# RH_T_SENSOR.net
KiCad netlist of a schematic drawn in EAGLE
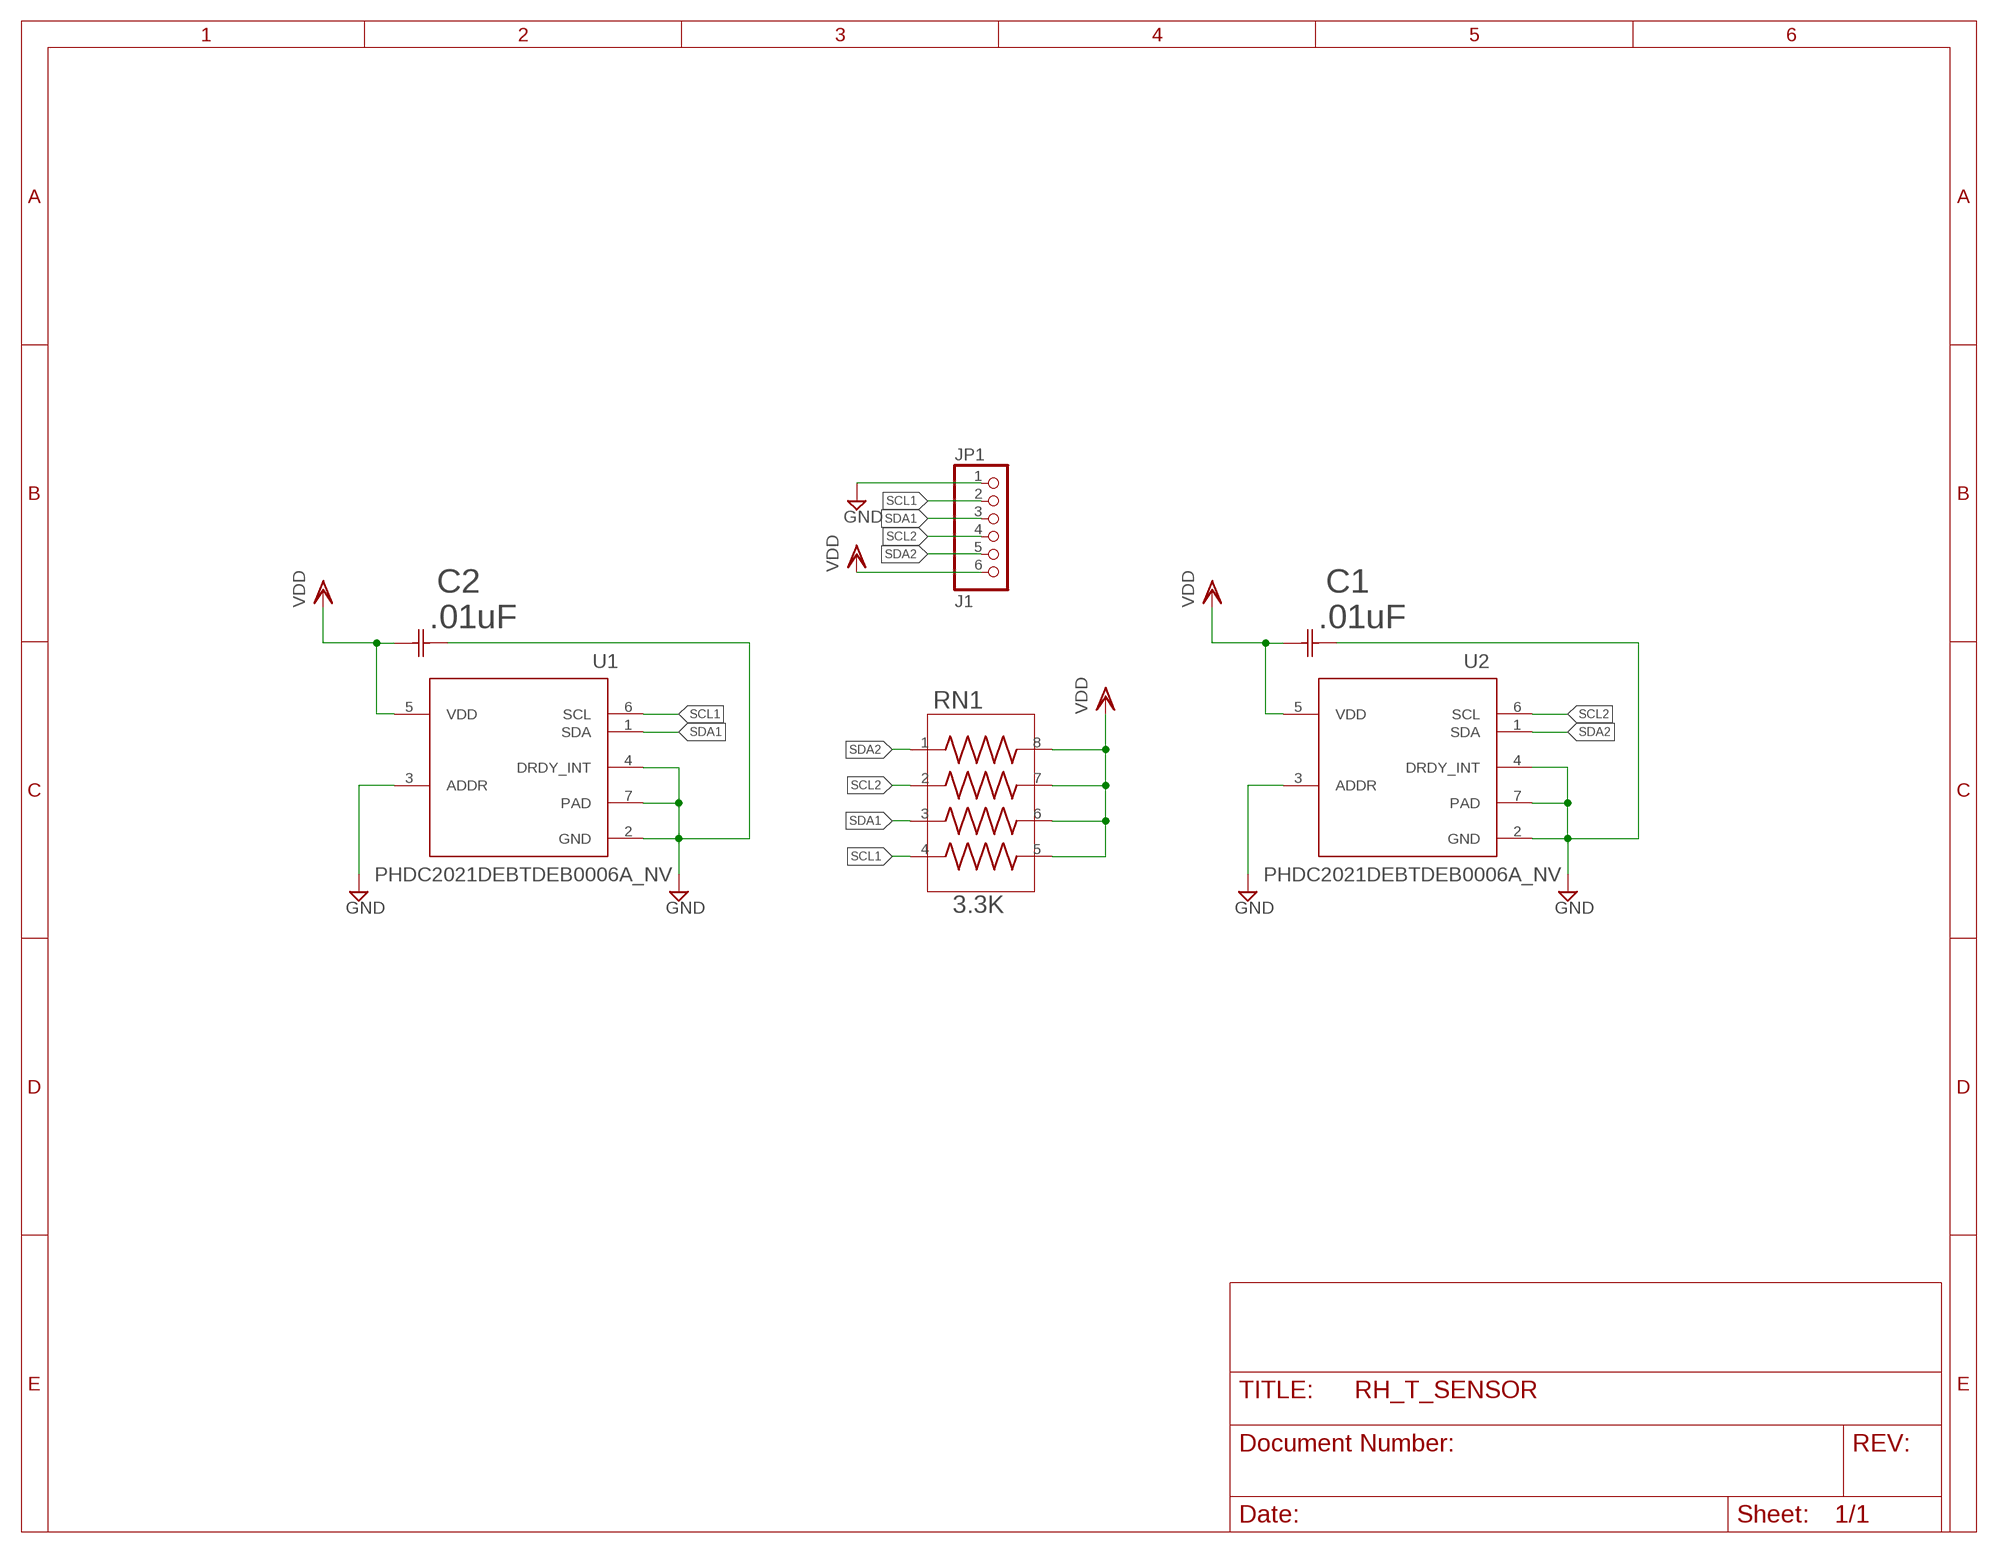
[diagram p0: schematic, sheet 1]

(export (version "E")
  (design (tool "Eeschema 10.0.6"))
  (components
    (comp (ref "C1")
      (value ".01uF")
      (footprint "eagle-import:0402_AVX")
      (fields
        (field (name "MANUFACTURER_PART_NUMBER") "0402YC104KAT2A")
        (field (name "COPYRIGHT") "Copyright (C) 2023 Ultra Librarian. All rights reserved.")
      )
      (libsource (lib "eagle-import") (part "0402YC104KAT2A0402_AVX"))
    )
    (comp (ref "C2")
      (value ".01uF")
      (footprint "eagle-import:0402_AVX")
      (fields
        (field (name "MANUFACTURER_PART_NUMBER") "0402YC104KAT2A")
        (field (name "COPYRIGHT") "Copyright (C) 2023 Ultra Librarian. All rights reserved.")
      )
      (libsource (lib "eagle-import") (part "0402YC104KAT2A0402_AVX"))
    )
    (comp (ref "JP1")
      (value "J1")
      (footprint "eagle-import:1X06M")
      (libsource (lib "eagle-import") (part "PINHD-1X6M"))
    )
    (comp (ref "RN1")
      (value "3.3K")
      (footprint "eagle-import:RESCAF80P320X160X60-8N")
      (fields (field (name "MANUFACTURER") "Bourns"))
      (libsource (lib "eagle-import") (part "CAY16-332J4LF"))
    )
    (comp (ref "U1")
      (value "PHDC2021DEBTDEB0006A_NV")
      (footprint "eagle-import:DEB0006A_NV")
      (fields
        (field (name "MANUFACTURER_PART_NUMBER") "PHDC2021DEBT")
        (field (name "COPYRIGHT") "Copyright (C) 2023 Ultra Librarian. All rights reserved.")
      )
      (libsource (lib "eagle-import") (part "PHDC2021DEBTDEB0006A_NV"))
    )
    (comp (ref "U2")
      (value "PHDC2021DEBTDEB0006A_NV")
      (footprint "eagle-import:DEB0006A_NV")
      (fields
        (field (name "MANUFACTURER_PART_NUMBER") "PHDC2021DEBT")
        (field (name "COPYRIGHT") "Copyright (C) 2023 Ultra Librarian. All rights reserved.")
      )
      (libsource (lib "eagle-import") (part "PHDC2021DEBTDEB0006A_NV"))
    )
  )
  (nets
    (net (code "1") (name "GND") (class "Default")
      (node (ref "C1") (pin "2") (pinfunction "2_2") (pintype "passive"))
      (node (ref "C2") (pin "2") (pinfunction "2_2") (pintype "passive"))
      (node (ref "JP1") (pin "1") (pinfunction "1_1") (pintype "passive"))
      (node (ref "U1") (pin "2") (pinfunction "GND_2") (pintype "power_in"))
      (node (ref "U1") (pin "3") (pinfunction "ADDR_3") (pintype "power_in"))
      (node (ref "U1") (pin "4") (pinfunction "DRDY_INT_4") (pintype "power_in"))
      (node (ref "U1") (pin "7") (pinfunction "PAD_7") (pintype "power_in"))
      (node (ref "U2") (pin "2") (pinfunction "GND_2") (pintype "power_in"))
      (node (ref "U2") (pin "3") (pinfunction "ADDR_3") (pintype "power_in"))
      (node (ref "U2") (pin "4") (pinfunction "DRDY_INT_4") (pintype "power_in"))
      (node (ref "U2") (pin "7") (pinfunction "PAD_7") (pintype "power_in"))
    )
    (net (code "2") (name "SCL1") (class "Default")
      (node (ref "JP1") (pin "2") (pinfunction "2_2") (pintype "passive"))
      (node (ref "RN1") (pin "4") (pinfunction "4_4") (pintype "passive"))
      (node (ref "U1") (pin "6") (pinfunction "SCL_6") (pintype "open_collector"))
    )
    (net (code "3") (name "SCL2") (class "Default")
      (node (ref "JP1") (pin "4") (pinfunction "4_4") (pintype "passive"))
      (node (ref "RN1") (pin "2") (pinfunction "2_2") (pintype "passive"))
      (node (ref "U2") (pin "6") (pinfunction "SCL_6") (pintype "open_collector"))
    )
    (net (code "4") (name "SDA1") (class "Default")
      (node (ref "JP1") (pin "3") (pinfunction "3_3") (pintype "passive"))
      (node (ref "RN1") (pin "3") (pinfunction "3_3") (pintype "passive"))
      (node (ref "U1") (pin "1") (pinfunction "SDA_1") (pintype "bidirectional"))
    )
    (net (code "5") (name "SDA2") (class "Default")
      (node (ref "JP1") (pin "5") (pinfunction "5_5") (pintype "passive"))
      (node (ref "RN1") (pin "1") (pinfunction "1_1") (pintype "passive"))
      (node (ref "U2") (pin "1") (pinfunction "SDA_1") (pintype "bidirectional"))
    )
    (net (code "6") (name "VDD") (class "Default")
      (node (ref "C1") (pin "1") (pinfunction "1_1") (pintype "passive"))
      (node (ref "C2") (pin "1") (pinfunction "1_1") (pintype "passive"))
      (node (ref "JP1") (pin "6") (pinfunction "6_6") (pintype "passive"))
      (node (ref "RN1") (pin "5") (pinfunction "5_5") (pintype "passive"))
      (node (ref "RN1") (pin "6") (pinfunction "6_6") (pintype "passive"))
      (node (ref "RN1") (pin "7") (pinfunction "7_7") (pintype "passive"))
      (node (ref "RN1") (pin "8") (pinfunction "8_8") (pintype "passive"))
      (node (ref "U1") (pin "5") (pinfunction "VDD_5") (pintype "power_in"))
      (node (ref "U2") (pin "5") (pinfunction "VDD_5") (pintype "power_in"))
    )
  )
)
